# Soccer-Robot_V1_2.net
KiCad netlist of a schematic drawn in EAGLE
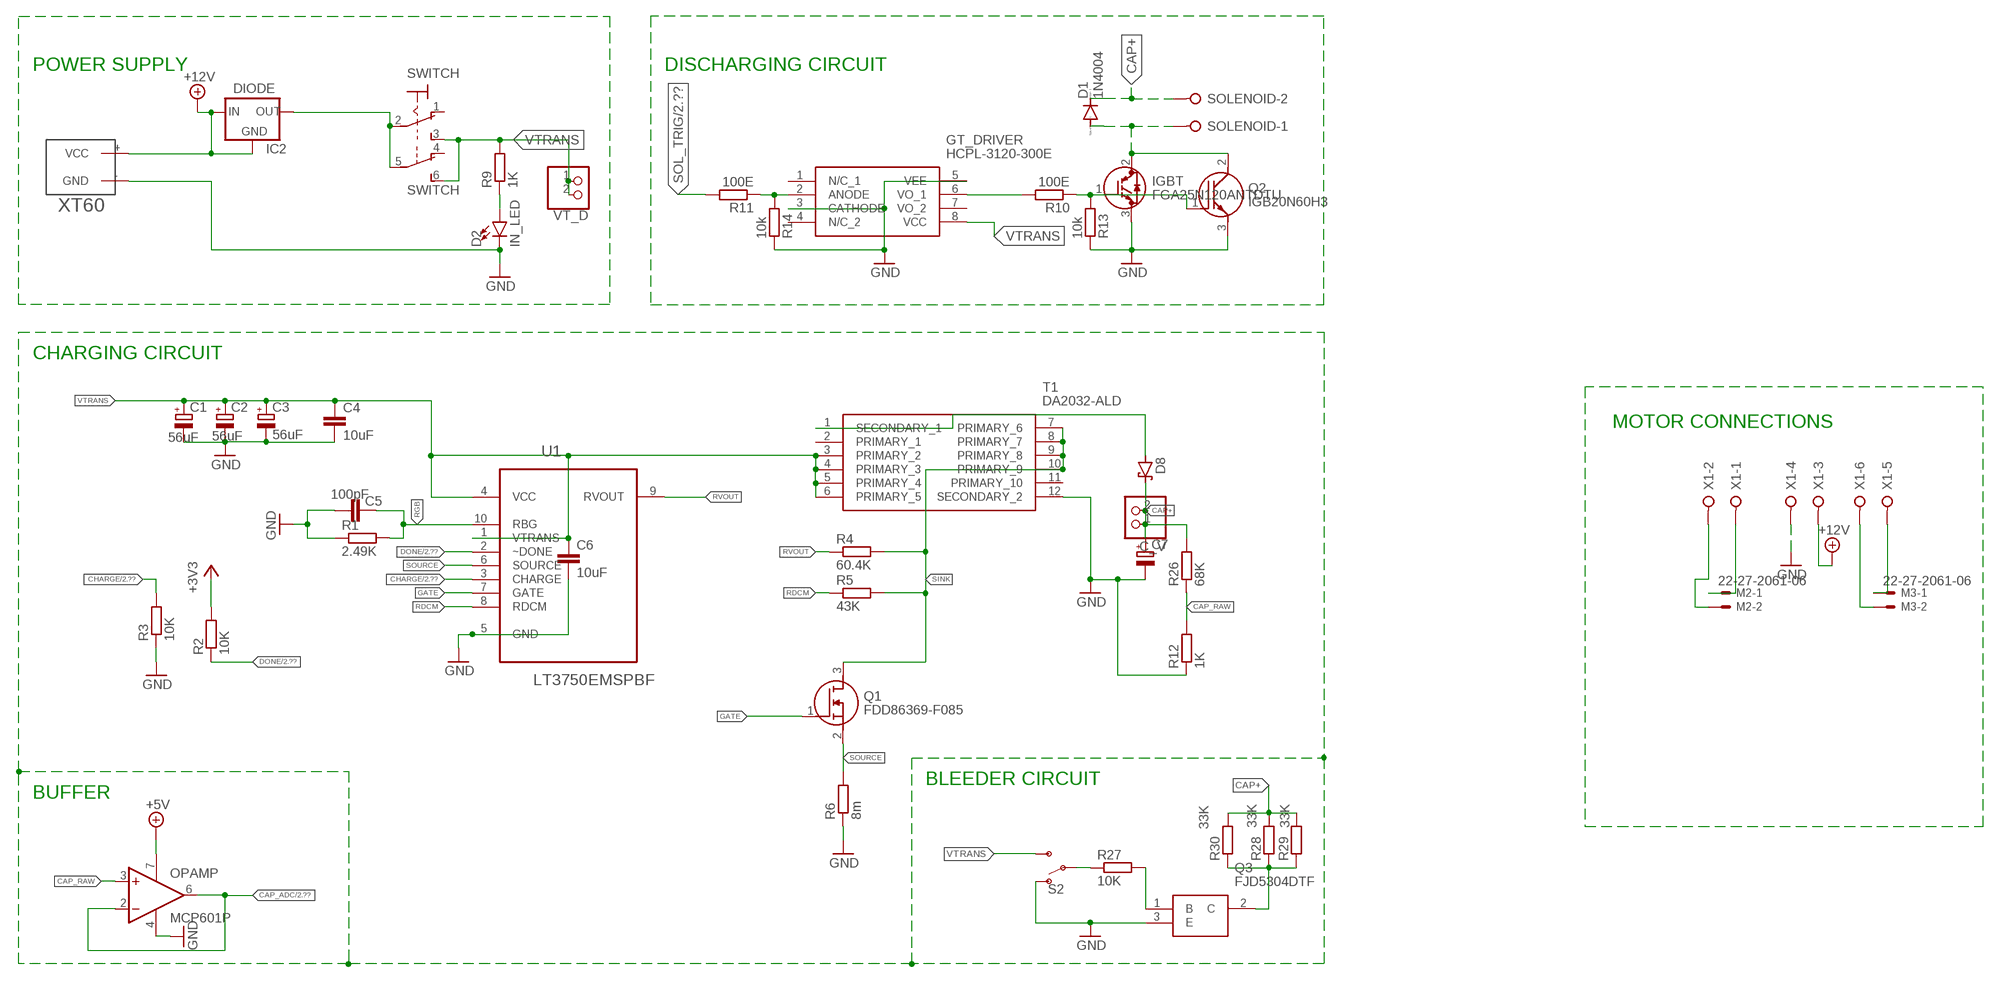
[diagram p0: schematic, sheet 1]
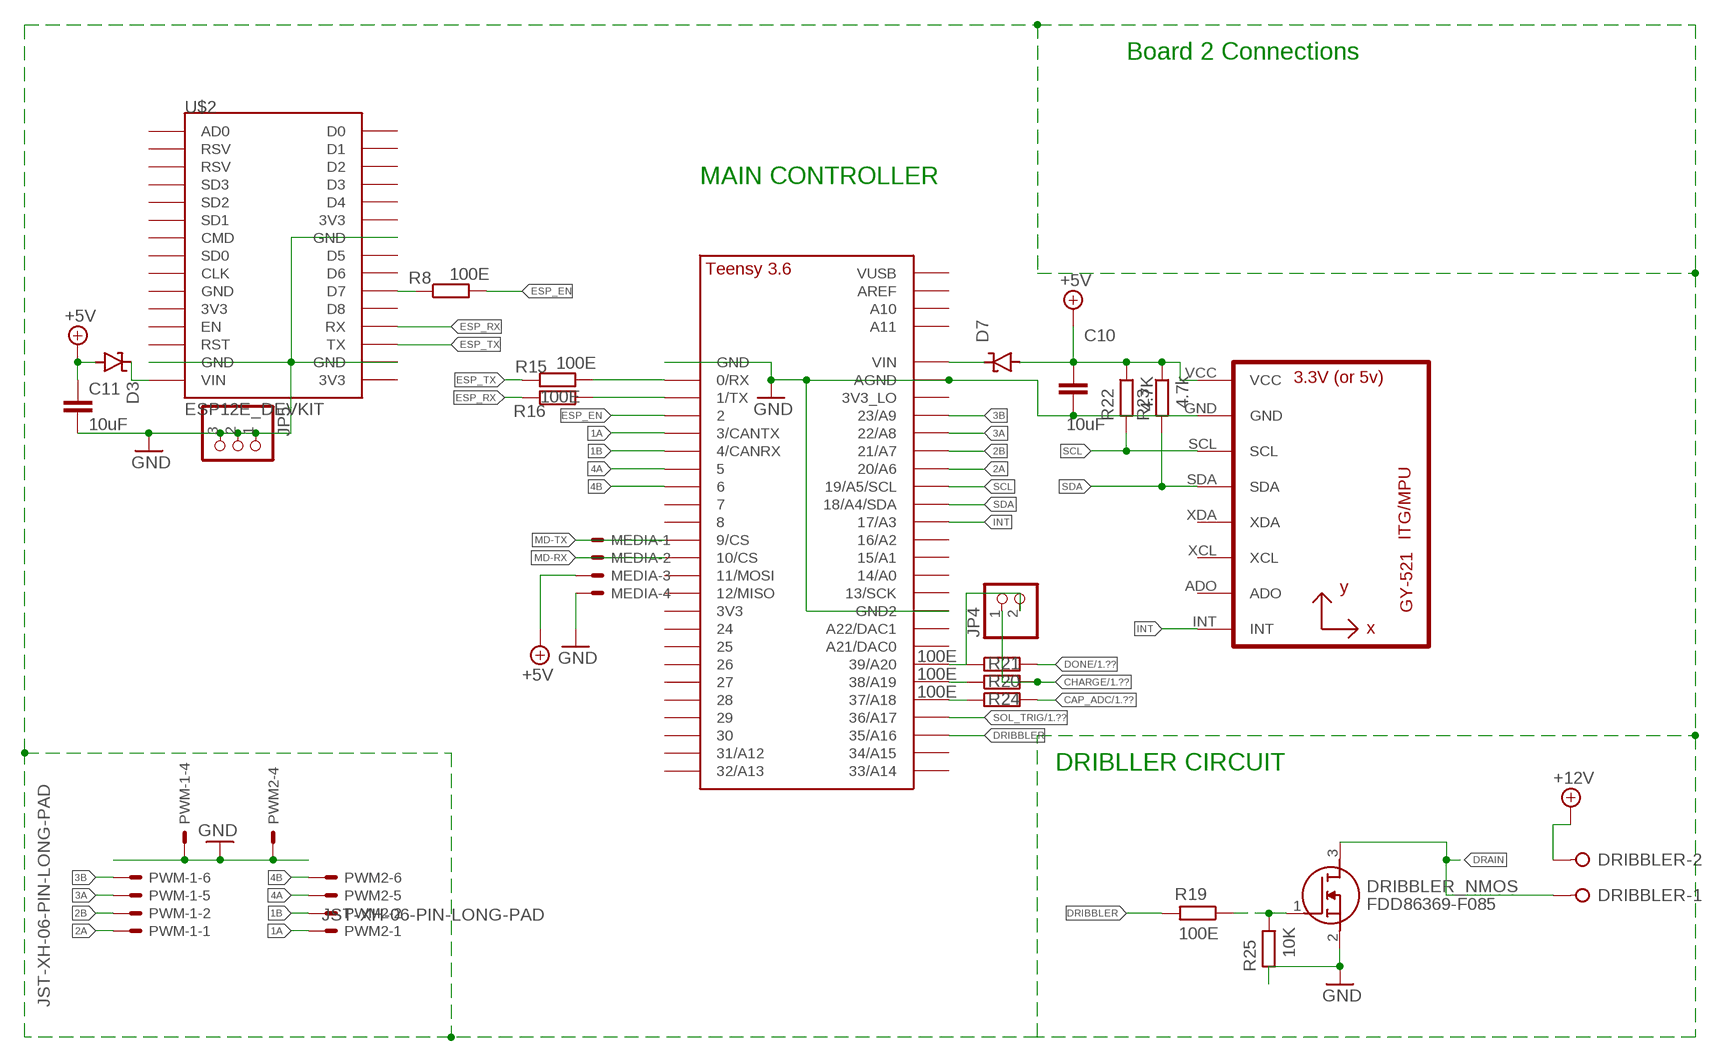
[diagram p1: schematic, sheet 2, part 1 of 2]
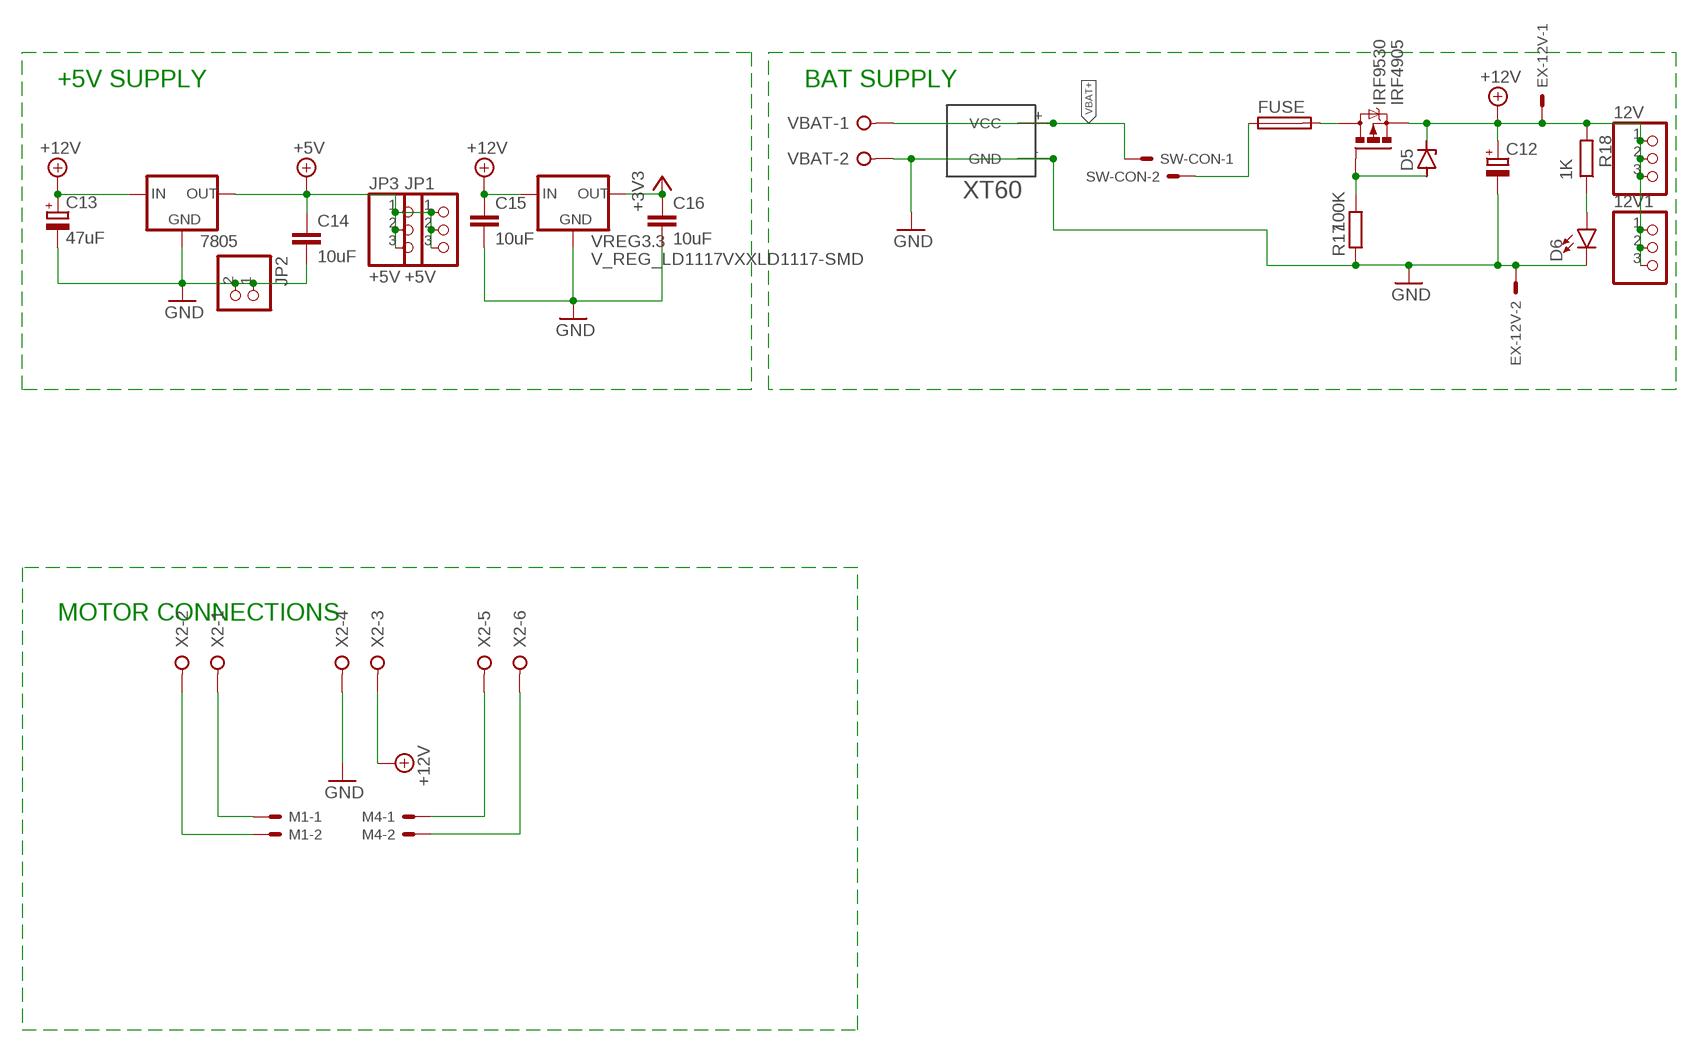
[diagram p2: schematic, sheet 2, part 2 of 2]

(export (version "E")
  (design (tool "Eeschema 10.0.6"))
  (components
    (comp (ref "12V")
      (value "PINHD-1X3")
      (footprint "eagle-import:1X03")
      (libsource (lib "eagle-import") (part "PINHD-1X3"))
    )
    (comp (ref "12V1")
      (value "PINHD-1X3")
      (footprint "eagle-import:1X03")
      (libsource (lib "eagle-import") (part "PINHD-1X3"))
    )
    (comp (ref "7805")
      (value "78XXS")
      (footprint "eagle-import:78XXS")
      (libsource (lib "eagle-import") (part "78XXS"))
    )
    (comp (ref "C10")
      (value "10uF")
      (footprint "eagle-import:C1206")
      (libsource (lib "eagle-import") (part "C-EUC1206"))
    )
    (comp (ref "C11")
      (value "10uF")
      (footprint "eagle-import:C1206")
      (libsource (lib "eagle-import") (part "C-EUC1206"))
    )
    (comp (ref "C12")
      (value "CPOL-EUE2.5-7")
      (footprint "eagle-import:E2,5-7")
      (libsource (lib "eagle-import") (part "CPOL-EUE2.5-7"))
    )
    (comp (ref "C13")
      (value "47uF")
      (footprint "eagle-import:E2,5-7")
      (libsource (lib "eagle-import") (part "CPOL-EUE2.5-7"))
    )
    (comp (ref "C14")
      (value "10uF")
      (footprint "eagle-import:C1206")
      (libsource (lib "eagle-import") (part "C-EUC1206"))
    )
    (comp (ref "C15")
      (value "10uF")
      (footprint "eagle-import:C1206")
      (libsource (lib "eagle-import") (part "C-EUC1206"))
    )
    (comp (ref "C16")
      (value "10uF")
      (footprint "eagle-import:C1206")
      (libsource (lib "eagle-import") (part "C-EUC1206"))
    )
    (comp (ref "D3")
      (value "SUPPRESSOR-SMBG")
      (footprint "eagle-import:SMBG")
      (libsource (lib "eagle-import") (part "SUPPRESSOR-SMBG"))
    )
    (comp (ref "D5")
      (value "ZENER-DIODEDO41Z10")
      (footprint "eagle-import:DO41Z10")
      (libsource (lib "eagle-import") (part "ZENER-DIODEDO41Z10"))
    )
    (comp (ref "D6")
      (value "LED5MM")
      (footprint "eagle-import:LED_5MM")
      (libsource (lib "eagle-import") (part "LED5MM"))
    )
    (comp (ref "D7")
      (value "SUPPRESSOR-SMBG")
      (footprint "eagle-import:SMBG")
      (libsource (lib "eagle-import") (part "SUPPRESSOR-SMBG"))
    )
    (comp (ref "DRIBBLER")
      (value "W237-02P")
      (footprint "eagle-import:W237-132")
      (libsource (lib "eagle-import") (part "W237-02P"))
    )
    (comp (ref "DRIBBLER_NMOS")
      (value "FDD86369-F085")
      (footprint "eagle-import:DPAK3-CASE-369AS")
      (fields (field (name "MOUSER_PART_NUMBER") "512-FDD86369_F085"))
      (libsource (lib "eagle-import") (part "FDD86369-F085"))
    )
    (comp (ref "EX-12V")
      (value "KK-156-2")
      (footprint "eagle-import:KK-156-2")
      (fields (field (name "MF") "MOLEX"))
      (libsource (lib "eagle-import") (part "KK-156-2"))
    )
    (comp (ref "FUSE")
      (value "SH22,5A")
      (footprint "eagle-import:SH22,5A")
      (fields (field (name "MPN") "0031.7701.11"))
      (libsource (lib "eagle-import") (part "SH22,5A"))
    )
    (comp (ref "IRF4905")
      (value "IRF9530")
      (footprint "eagle-import:TO220BV")
      (libsource (lib "eagle-import") (part "IRF9530"))
    )
    (comp (ref "JP1")
      (value "+5V")
      (footprint "eagle-import:1X03")
      (libsource (lib "eagle-import") (part "PINHD-1X3"))
    )
    (comp (ref "JP2")
      (value "PINHD-1X2")
      (footprint "eagle-import:1X02")
      (libsource (lib "eagle-import") (part "PINHD-1X2"))
    )
    (comp (ref "JP3")
      (value "+5V")
      (footprint "eagle-import:1X03")
      (libsource (lib "eagle-import") (part "PINHD-1X3"))
    )
    (comp (ref "JP4")
      (value "PINHD-1X2")
      (footprint "eagle-import:1X02")
      (libsource (lib "eagle-import") (part "PINHD-1X2"))
    )
    (comp (ref "JP5")
      (value "PINHD-1X3")
      (footprint "eagle-import:1X03")
      (libsource (lib "eagle-import") (part "PINHD-1X3"))
    )
    (comp (ref "M1")
      (value "22-27-2061-06")
      (footprint "eagle-import:6410-06")
      (fields (field (name "MF") "MOLEX"))
      (libsource (lib "eagle-import") (part "22-?-0627-2061"))
    )
    (comp (ref "M4")
      (value "22-27-2061-06")
      (footprint "eagle-import:6410-06")
      (fields (field (name "MF") "MOLEX"))
      (libsource (lib "eagle-import") (part "22-?-0627-2061"))
    )
    (comp (ref "MEDIA")
      (value "JST-XH-04-PIN-LONG-PAD")
      (footprint "eagle-import:JST-XH-04-PACKAGE-LONG-PAD")
      (libsource (lib "eagle-import") (part "JST-XH-04-PIN-LONG-PAD"))
    )
    (comp (ref "PWM-1")
      (value "JST-XH-06-PIN-LONG-PAD")
      (footprint "eagle-import:JST-XH-06-PACKAGE-LONG-PAD")
      (libsource (lib "eagle-import") (part "JST-XH-06-PIN-LONG-PAD"))
    )
    (comp (ref "PWM2")
      (value "JST-XH-06-PIN-LONG-PAD")
      (footprint "eagle-import:JST-XH-06-PACKAGE-LONG-PAD")
      (libsource (lib "eagle-import") (part "JST-XH-06-PIN-LONG-PAD"))
    )
    (comp (ref "R8")
      (value "100E")
      (footprint "eagle-import:M1206")
      (libsource (lib "eagle-import") (part "R-EU_M1206"))
    )
    (comp (ref "R15")
      (value "100E")
      (footprint "eagle-import:M1206")
      (libsource (lib "eagle-import") (part "R-EU_M1206"))
    )
    (comp (ref "R16")
      (value "100E")
      (footprint "eagle-import:M1206")
      (libsource (lib "eagle-import") (part "R-EU_M1206"))
    )
    (comp (ref "R17")
      (value "100K")
      (footprint "eagle-import:M1206")
      (libsource (lib "eagle-import") (part "R-EU_M1206"))
    )
    (comp (ref "R18")
      (value "1K")
      (footprint "eagle-import:M1206")
      (libsource (lib "eagle-import") (part "R-EU_M1206"))
    )
    (comp (ref "R19")
      (value "100E")
      (footprint "eagle-import:M1206")
      (libsource (lib "eagle-import") (part "R-EU_M1206"))
    )
    (comp (ref "R20")
      (value "100E")
      (footprint "eagle-import:M1206")
      (libsource (lib "eagle-import") (part "R-EU_M1206"))
    )
    (comp (ref "R21")
      (value "100E")
      (footprint "eagle-import:M1206")
      (libsource (lib "eagle-import") (part "R-EU_M1206"))
    )
    (comp (ref "R22")
      (value "4.7K")
      (footprint "eagle-import:M1206")
      (libsource (lib "eagle-import") (part "R-EU_M1206"))
    )
    (comp (ref "R23")
      (value "4.7k")
      (footprint "eagle-import:M1206")
      (libsource (lib "eagle-import") (part "R-EU_M1206"))
    )
    (comp (ref "R24")
      (value "100E")
      (footprint "eagle-import:M1206")
      (libsource (lib "eagle-import") (part "R-EU_M1206"))
    )
    (comp (ref "R25")
      (value "10K")
      (footprint "eagle-import:M1206")
      (libsource (lib "eagle-import") (part "R-EU_M1206"))
    )
    (comp (ref "SW-CON")
      (value "KK-156-2")
      (footprint "eagle-import:KK-156-2")
      (fields (field (name "MF") "MOLEX"))
      (libsource (lib "eagle-import") (part "KK-156-2"))
    )
    (comp (ref "U$2")
      (value "ESP12E_DEVKIT")
      (footprint "eagle-import:ESP12E_DEVKIT")
      (libsource (lib "eagle-import") (part "ESP12E_DEVKIT"))
    )
    (comp (ref "U$3")
      (value "TEENSY_3.5/3.6_BASIC")
      (footprint "eagle-import:TEENSY_3.5_3.6_BASIC")
      (libsource (lib "eagle-import") (part "TEENSY_3.5/3.6_BASIC"))
    )
    (comp (ref "U2")
      (value "GY-521MPU6050")
      (footprint "eagle-import:GY-521")
      (libsource (lib "eagle-import") (part "GY-521MPU6050"))
    )
    (comp (ref "VBAT")
      (value "W237-02P")
      (footprint "eagle-import:W237-132")
      (libsource (lib "eagle-import") (part "W237-02P"))
    )
    (comp (ref "VBAT2")
      (value "XT60")
      (footprint "eagle-import:XT60")
      (libsource (lib "eagle-import") (part "XT60"))
    )
    (comp (ref "VREG3.3")
      (value "V_REG_LD1117VXXLD1117-SMD")
      (footprint "eagle-import:SOT223")
      (libsource (lib "eagle-import") (part "V_REG_LD1117VXXLD1117-SMD"))
    )
    (comp (ref "X2")
      (value "W237-06P")
      (footprint "eagle-import:W237-6P")
      (libsource (lib "eagle-import") (part "W237-06P"))
    )
    (comp (ref "C1")
      (value "56uF")
      (footprint "eagle-import:E2,5-5")
      (libsource (lib "eagle-import") (part "CPOL-EUE2.5-5"))
    )
    (comp (ref "C2")
      (value "56uF")
      (footprint "eagle-import:E2,5-5")
      (libsource (lib "eagle-import") (part "CPOL-EUE2.5-5"))
    )
    (comp (ref "C3")
      (value "56uF")
      (footprint "eagle-import:E2,5-5")
      (libsource (lib "eagle-import") (part "CPOL-EUE2.5-5"))
    )
    (comp (ref "C4")
      (value "10uF")
      (footprint "eagle-import:C1206")
      (libsource (lib "eagle-import") (part "C-EUC1206"))
    )
    (comp (ref "C5")
      (value "100pF")
      (footprint "eagle-import:C1206")
      (libsource (lib "eagle-import") (part "C-EUC1206"))
    )
    (comp (ref "C6")
      (value "10uF")
      (footprint "eagle-import:C1206")
      (libsource (lib "eagle-import") (part "C-EUC1206"))
    )
    (comp (ref "C7")
      (value "CPOL-EUE10-30")
      (footprint "eagle-import:EB30D")
      (libsource (lib "eagle-import") (part "CPOL-EUE10-30"))
    )
    (comp (ref "C_V")
      (value "PINHD-1X2")
      (footprint "eagle-import:1X02")
      (libsource (lib "eagle-import") (part "PINHD-1X2"))
    )
    (comp (ref "D1")
      (value "1N4004")
      (footprint "eagle-import:DO41-10")
      (libsource (lib "eagle-import") (part "1N4004"))
    )
    (comp (ref "D2")
      (value "IN_LED")
      (footprint "eagle-import:LED_5MM")
      (libsource (lib "eagle-import") (part "LED5MM"))
    )
    (comp (ref "D8")
      (value "SCHOTTKY-DIODESMC")
      (footprint "eagle-import:SMC")
      (libsource (lib "eagle-import") (part "SCHOTTKY-DIODESMC"))
    )
    (comp (ref "GT_DRIVER")
      (value "HCPL-3120-300E")
      (footprint "eagle-import:HCPL-3120-GULL-WING")
      (fields (field (name "MOUSER_PART_NUMBER") "630-HCPL-3120-300E"))
      (libsource (lib "eagle-import") (part "HCPL-3120-300E"))
    )
    (comp (ref "IC2")
      (value "DIODE")
      (footprint "eagle-import:TO252")
      (libsource (lib "eagle-import") (part "LM1117TO252"))
    )
    (comp (ref "IGBT")
      (value "FGA25N120ANTDTU")
      (footprint "eagle-import:TO545P500X1560X2420-3P")
      (fields (field (name "MOUSER_PART_NUMBER") "512-FGA25N120ANTDTU"))
      (libsource (lib "eagle-import") (part "FGA25N120ANTDTU"))
    )
    (comp (ref "M2")
      (value "22-27-2061-06")
      (footprint "eagle-import:6410-06")
      (fields (field (name "MF") "MOLEX"))
      (libsource (lib "eagle-import") (part "22-?-0627-2061"))
    )
    (comp (ref "M3")
      (value "22-27-2061-06")
      (footprint "eagle-import:6410-06")
      (fields (field (name "MF") "MOLEX"))
      (libsource (lib "eagle-import") (part "22-?-0627-2061"))
    )
    (comp (ref "OPAMP")
      (value "MCP601P")
      (footprint "eagle-import:DIL08")
      (libsource (lib "eagle-import") (part "MCP601P"))
    )
    (comp (ref "Q1")
      (value "FDD86369-F085")
      (footprint "eagle-import:DPAK3-CASE-369AS")
      (fields (field (name "MOUSER_PART_NUMBER") "512-FDD86369_F085"))
      (libsource (lib "eagle-import") (part "FDD86369-F085"))
    )
    (comp (ref "Q2")
      (value "IGB20N60H3")
      (footprint "eagle-import:IDB30E60")
      (fields (field (name "MOUSER_PART_NUMBER") "726-IGB20N60H3"))
      (libsource (lib "eagle-import") (part "IGB20N60H3"))
    )
    (comp (ref "Q3")
      (value "FJD5304DTF")
      (footprint "eagle-import:FJD5304DTF")
      (fields (field (name "MOUSER_PART_NUMBER") "512-FJD5304DTF"))
      (libsource (lib "eagle-import") (part "FJD5304DTF"))
    )
    (comp (ref "R1")
      (value "2.49K")
      (footprint "eagle-import:M1206")
      (libsource (lib "eagle-import") (part "R-EU_M1206"))
    )
    (comp (ref "R2")
      (value "10K")
      (footprint "eagle-import:M1206")
      (libsource (lib "eagle-import") (part "R-EU_M1206"))
    )
    (comp (ref "R3")
      (value "10K")
      (footprint "eagle-import:M1206")
      (libsource (lib "eagle-import") (part "R-EU_M1206"))
    )
    (comp (ref "R4")
      (value "60.4K")
      (footprint "eagle-import:M1206")
      (libsource (lib "eagle-import") (part "R-EU_M1206"))
    )
    (comp (ref "R5")
      (value "43K")
      (footprint "eagle-import:M1206")
      (libsource (lib "eagle-import") (part "R-EU_M1206"))
    )
    (comp (ref "R6")
      (value "8m")
      (footprint "eagle-import:M1206")
      (libsource (lib "eagle-import") (part "R-EU_M1206"))
    )
    (comp (ref "R9")
      (value "1K")
      (footprint "eagle-import:M1206")
      (libsource (lib "eagle-import") (part "R-EU_M1206"))
    )
    (comp (ref "R10")
      (value "100E")
      (footprint "eagle-import:M1206")
      (libsource (lib "eagle-import") (part "R-EU_M1206"))
    )
    (comp (ref "R11")
      (value "100E")
      (footprint "eagle-import:M1206")
      (libsource (lib "eagle-import") (part "R-EU_M1206"))
    )
    (comp (ref "R12")
      (value "1K")
      (footprint "eagle-import:M1206")
      (libsource (lib "eagle-import") (part "R-EU_M1206"))
    )
    (comp (ref "R13")
      (value "10k")
      (footprint "eagle-import:M1206")
      (libsource (lib "eagle-import") (part "R-EU_M1206"))
    )
    (comp (ref "R14")
      (value "10k")
      (footprint "eagle-import:M1206")
      (libsource (lib "eagle-import") (part "R-EU_M1206"))
    )
    (comp (ref "R26")
      (value "68K")
      (footprint "eagle-import:M1206")
      (libsource (lib "eagle-import") (part "R-EU_M1206"))
    )
    (comp (ref "R27")
      (value "10K")
      (footprint "eagle-import:M1206")
      (libsource (lib "eagle-import") (part "R-EU_M1206"))
    )
    (comp (ref "R28")
      (value "33K")
      (footprint "eagle-import:M1206")
      (libsource (lib "eagle-import") (part "R-EU_M1206"))
    )
    (comp (ref "R29")
      (value "33K")
      (footprint "eagle-import:M1206")
      (libsource (lib "eagle-import") (part "R-EU_M1206"))
    )
    (comp (ref "R30")
      (value "33K")
      (footprint "eagle-import:M1206")
      (libsource (lib "eagle-import") (part "R-EU_M1206"))
    )
    (comp (ref "S2")
      (value "SWITCH-SPDT-PTH-11.6X4.0MM")
      (footprint "eagle-import:SWITCH_SPDT_PTH_11.6X4.0MM")
      (libsource (lib "eagle-import") (part "SWITCH-SPDT-PTH-11.6X4.0MM"))
    )
    (comp (ref "SOLENOID")
      (value "W237-02P")
      (footprint "eagle-import:W237-132")
      (libsource (lib "eagle-import") (part "W237-02P"))
    )
    (comp (ref "SWITCH")
      (value "320-938")
      (footprint "eagle-import:320-938")
      (libsource (lib "eagle-import") (part "320-938"))
    )
    (comp (ref "T1")
      (value "DA2032-ALD")
      (footprint "eagle-import:SOP250P2197X889-12N")
      (fields (field (name "MOUSER_PART_NUMBER") "994-DA2032-ALD"))
      (libsource (lib "eagle-import") (part "DA2032-ALD"))
    )
    (comp (ref "U$1")
      (value "XT60")
      (footprint "eagle-import:XT60")
      (libsource (lib "eagle-import") (part "XT60"))
    )
    (comp (ref "U1")
      (value "LT3750EMSPBF")
      (footprint "eagle-import:SOP50P490X110-10N")
      (fields (field (name "MPN") "LT3750EMS#PBF"))
      (libsource (lib "eagle-import") (part "LT3750EMSPBF"))
    )
    (comp (ref "VT_D")
      (value "PINHD-1X2")
      (footprint "eagle-import:1X02")
      (libsource (lib "eagle-import") (part "PINHD-1X2"))
    )
    (comp (ref "X1")
      (value "W237-06P")
      (footprint "eagle-import:W237-6P")
      (libsource (lib "eagle-import") (part "W237-06P"))
    )
  )
  (nets
    (net (code "1") (name "+3V3") (class "Default")
      (node (ref "C16") (pin "1") (pinfunction "1_1") (pintype "passive"))
      (node (ref "R2") (pin "2") (pinfunction "2_2") (pintype "passive"))
      (node (ref "VREG3.3") (pin "2") (pinfunction "OUT_2") (pintype "passive"))
      (node (ref "VREG3.3") (pin "4") (pinfunction "OUT_4") (pintype "passive"))
    )
    (net (code "2") (name "+5V") (class "Default")
      (node (ref "7805") (pin "OUT") (pinfunction "OUT_OUT") (pintype "passive"))
      (node (ref "C10") (pin "1") (pinfunction "1_1") (pintype "passive"))
      (node (ref "C11") (pin "1") (pinfunction "1_1") (pintype "passive"))
      (node (ref "C14") (pin "1") (pinfunction "1_1") (pintype "passive"))
      (node (ref "D3") (pin "A") (pinfunction "A_A") (pintype "passive"))
      (node (ref "D7") (pin "A") (pinfunction "A_A") (pintype "passive"))
      (node (ref "JP1") (pin "1") (pinfunction "1_1") (pintype "passive"))
      (node (ref "JP1") (pin "2") (pinfunction "2_2") (pintype "passive"))
      (node (ref "JP1") (pin "3") (pinfunction "3_3") (pintype "passive"))
      (node (ref "JP3") (pin "1") (pinfunction "1_1") (pintype "passive"))
      (node (ref "JP3") (pin "2") (pinfunction "2_2") (pintype "passive"))
      (node (ref "JP3") (pin "3") (pinfunction "3_3") (pintype "passive"))
      (node (ref "MEDIA") (pin "3") (pinfunction "S_3") (pintype "passive"))
      (node (ref "OPAMP") (pin "7") (pinfunction "V+_7") (pintype "power_in"))
      (node (ref "R22") (pin "1") (pinfunction "1_1") (pintype "passive"))
      (node (ref "R23") (pin "1") (pinfunction "1_1") (pintype "passive"))
      (node (ref "U2") (pin "VCC") (pinfunction "VCC_VCC") (pintype "bidirectional"))
    )
    (net (code "3") (name "+12V") (class "Default")
      (node (ref "12V") (pin "1") (pinfunction "1_1") (pintype "passive"))
      (node (ref "12V") (pin "2") (pinfunction "2_2") (pintype "passive"))
      (node (ref "12V") (pin "3") (pinfunction "3_3") (pintype "passive"))
      (node (ref "12V1") (pin "1") (pinfunction "1_1") (pintype "passive"))
      (node (ref "12V1") (pin "2") (pinfunction "2_2") (pintype "passive"))
      (node (ref "12V1") (pin "3") (pinfunction "3_3") (pintype "passive"))
      (node (ref "7805") (pin "IN") (pinfunction "IN_IN") (pintype "input"))
      (node (ref "C12") (pin "+") (pinfunction "+_+") (pintype "passive"))
      (node (ref "C13") (pin "+") (pinfunction "+_+") (pintype "passive"))
      (node (ref "C15") (pin "1") (pinfunction "1_1") (pintype "passive"))
      (node (ref "D5") (pin "C") (pinfunction "C_C") (pintype "passive"))
      (node (ref "DRIBBLER") (pin "2") (pinfunction "KL_2") (pintype "passive"))
      (node (ref "EX-12V") (pin "1") (pinfunction "S_1") (pintype "passive"))
      (node (ref "IC2") (pin "1") (pinfunction "GND_1") (pintype "input"))
      (node (ref "IC2") (pin "2") (pinfunction "IN_2") (pintype "input"))
      (node (ref "IRF4905") (pin "S") (pinfunction "S_S") (pintype "passive"))
      (node (ref "R18") (pin "2") (pinfunction "2_2") (pintype "passive"))
      (node (ref "U$1") (pin "+") (pinfunction "VCC_+") (pintype "bidirectional"))
      (node (ref "VREG3.3") (pin "3") (pinfunction "IN_3") (pintype "input"))
      (node (ref "X1") (pin "3") (pinfunction "KL_3") (pintype "passive"))
      (node (ref "X2") (pin "3") (pinfunction "KL_3") (pintype "passive"))
    )
    (net (code "4") (name "1A") (class "Default")
      (node (ref "PWM2") (pin "1") (pinfunction "S_1") (pintype "passive"))
      (node (ref "U$3") (pin "3/CANTX") (pinfunction "3/CANTX_3/CANTX") (pintype "bidirectional"))
    )
    (net (code "5") (name "1B") (class "Default")
      (node (ref "PWM2") (pin "2") (pinfunction "S_2") (pintype "passive"))
      (node (ref "U$3") (pin "4/CANRX") (pinfunction "4/CANRX_4/CANRX") (pintype "bidirectional"))
    )
    (net (code "6") (name "2A") (class "Default")
      (node (ref "PWM-1") (pin "1") (pinfunction "S_1") (pintype "passive"))
      (node (ref "U$3") (pin "20/A6") (pinfunction "20/A6_20/A6") (pintype "bidirectional"))
    )
    (net (code "7") (name "2B") (class "Default")
      (node (ref "PWM-1") (pin "2") (pinfunction "S_2") (pintype "passive"))
      (node (ref "U$3") (pin "21/A7") (pinfunction "21/A7_21/A7") (pintype "bidirectional"))
    )
    (net (code "8") (name "3A") (class "Default")
      (node (ref "PWM-1") (pin "5") (pinfunction "S_5") (pintype "passive"))
      (node (ref "U$3") (pin "22/A8") (pinfunction "22/A8_22/A8") (pintype "bidirectional"))
    )
    (net (code "9") (name "3B") (class "Default")
      (node (ref "PWM-1") (pin "6") (pinfunction "S_6") (pintype "passive"))
      (node (ref "U$3") (pin "23/A9") (pinfunction "23/A9_23/A9") (pintype "bidirectional"))
    )
    (net (code "10") (name "4A") (class "Default")
      (node (ref "PWM2") (pin "5") (pinfunction "S_5") (pintype "passive"))
      (node (ref "U$3") (pin "5") (pinfunction "5_5") (pintype "bidirectional"))
    )
    (net (code "11") (name "4B") (class "Default")
      (node (ref "PWM2") (pin "6") (pinfunction "S_6") (pintype "passive"))
      (node (ref "U$3") (pin "6") (pinfunction "6_6") (pintype "bidirectional"))
    )
    (net (code "12") (name "CAP+") (class "Default")
      (node (ref "C7") (pin "+") (pinfunction "+_+") (pintype "passive"))
      (node (ref "C_V") (pin "1") (pinfunction "1_1") (pintype "passive"))
      (node (ref "C_V") (pin "2") (pinfunction "2_2") (pintype "passive"))
      (node (ref "D1") (pin "C") (pinfunction "C_C") (pintype "passive"))
      (node (ref "D8") (pin "C") (pinfunction "C_C") (pintype "passive"))
      (node (ref "R26") (pin "2") (pinfunction "2_2") (pintype "passive"))
      (node (ref "R28") (pin "2") (pinfunction "2_2") (pintype "passive"))
      (node (ref "R29") (pin "2") (pinfunction "2_2") (pintype "passive"))
      (node (ref "R30") (pin "2") (pinfunction "2_2") (pintype "passive"))
      (node (ref "SOLENOID") (pin "2") (pinfunction "KL_2") (pintype "passive"))
    )
    (net (code "13") (name "CAP_ADC") (class "Default")
      (node (ref "OPAMP") (pin "2") (pinfunction "-IN_2") (pintype "input"))
      (node (ref "OPAMP") (pin "6") (pinfunction "OUT_6") (pintype "output"))
      (node (ref "R24") (pin "2") (pinfunction "2_2") (pintype "passive"))
    )
    (net (code "14") (name "CAP_RAW") (class "Default")
      (node (ref "OPAMP") (pin "3") (pinfunction "+IN_3") (pintype "input"))
      (node (ref "R12") (pin "2") (pinfunction "2_2") (pintype "passive"))
      (node (ref "R26") (pin "1") (pinfunction "1_1") (pintype "passive"))
    )
    (net (code "15") (name "CHARGE") (class "Default")
      (node (ref "JP4") (pin "1") (pinfunction "1_1") (pintype "passive"))
      (node (ref "R20") (pin "2") (pinfunction "2_2") (pintype "passive"))
      (node (ref "R3") (pin "2") (pinfunction "2_2") (pintype "passive"))
      (node (ref "U1") (pin "3") (pinfunction "CHARGE_3") (pintype "input"))
    )
    (net (code "16") (name "DONE") (class "Default")
      (node (ref "R2") (pin "1") (pinfunction "1_1") (pintype "passive"))
      (node (ref "R21") (pin "2") (pinfunction "2_2") (pintype "passive"))
      (node (ref "U1") (pin "2") (pinfunction "~{DONE}_2") (pintype "input"))
    )
    (net (code "17") (name "DRAIN") (class "Default")
      (node (ref "DRIBBLER") (pin "1") (pinfunction "KL_1") (pintype "passive"))
      (node (ref "DRIBBLER_NMOS") (pin "3") (pinfunction "D_3") (pintype "bidirectional"))
    )
    (net (code "18") (name "DRIBBLER") (class "Default")
      (node (ref "R19") (pin "2") (pinfunction "2_2") (pintype "passive"))
      (node (ref "U$3") (pin "35/A16") (pinfunction "35/A16_35/A16") (pintype "bidirectional"))
    )
    (net (code "19") (name "ESP_EN") (class "Default")
      (node (ref "R8") (pin "2") (pinfunction "2_2") (pintype "passive"))
      (node (ref "U$3") (pin "2") (pinfunction "2_2") (pintype "bidirectional"))
    )
    (net (code "20") (name "ESP_RX") (class "Default")
      (node (ref "R16") (pin "1") (pinfunction "1_1") (pintype "passive"))
      (node (ref "U$2") (pin "RX") (pinfunction "RX_RX") (pintype "bidirectional"))
    )
    (net (code "21") (name "ESP_TX") (class "Default")
      (node (ref "R15") (pin "1") (pinfunction "1_1") (pintype "passive"))
      (node (ref "U$2") (pin "TX") (pinfunction "TX_TX") (pintype "bidirectional"))
    )
    (net (code "22") (name "GATE") (class "Default")
      (node (ref "Q1") (pin "1") (pinfunction "G_1") (pintype "bidirectional"))
      (node (ref "U1") (pin "7") (pinfunction "GATE_7") (pintype "input"))
    )
    (net (code "23") (name "GND") (class "Default")
      (node (ref "7805") (pin "GND") (pinfunction "GND_GND") (pintype "input"))
      (node (ref "C1") (pin "-") (pinfunction "-_-") (pintype "passive"))
      (node (ref "C10") (pin "2") (pinfunction "2_2") (pintype "passive"))
      (node (ref "C11") (pin "2") (pinfunction "2_2") (pintype "passive"))
      (node (ref "C12") (pin "-") (pinfunction "-_-") (pintype "passive"))
      (node (ref "C13") (pin "-") (pinfunction "-_-") (pintype "passive"))
      (node (ref "C14") (pin "2") (pinfunction "2_2") (pintype "passive"))
      (node (ref "C15") (pin "2") (pinfunction "2_2") (pintype "passive"))
      (node (ref "C16") (pin "2") (pinfunction "2_2") (pintype "passive"))
      (node (ref "C2") (pin "-") (pinfunction "-_-") (pintype "passive"))
      (node (ref "C3") (pin "-") (pinfunction "-_-") (pintype "passive"))
      (node (ref "C4") (pin "2") (pinfunction "2_2") (pintype "passive"))
      (node (ref "C5") (pin "2") (pinfunction "2_2") (pintype "passive"))
      (node (ref "C6") (pin "2") (pinfunction "2_2") (pintype "passive"))
      (node (ref "C7") (pin "-") (pinfunction "-_-") (pintype "passive"))
      (node (ref "D2") (pin "K") (pinfunction "C_K") (pintype "passive"))
      (node (ref "D6") (pin "K") (pinfunction "C_K") (pintype "passive"))
      (node (ref "DRIBBLER_NMOS") (pin "2") (pinfunction "S_2") (pintype "bidirectional"))
      (node (ref "EX-12V") (pin "2") (pinfunction "S_2") (pintype "passive"))
      (node (ref "GT_DRIVER") (pin "3") (pinfunction "CATHODE_3") (pintype "bidirectional"))
      (node (ref "GT_DRIVER") (pin "5") (pinfunction "VEE_5") (pintype "bidirectional"))
      (node (ref "IGBT") (pin "3") (pinfunction "E_3") (pintype "bidirectional"))
      (node (ref "JP2") (pin "1") (pinfunction "1_1") (pintype "passive"))
      (node (ref "JP2") (pin "2") (pinfunction "2_2") (pintype "passive"))
      (node (ref "JP5") (pin "1") (pinfunction "1_1") (pintype "passive"))
      (node (ref "JP5") (pin "2") (pinfunction "2_2") (pintype "passive"))
      (node (ref "JP5") (pin "3") (pinfunction "3_3") (pintype "passive"))
      (node (ref "MEDIA") (pin "4") (pinfunction "S_4") (pintype "passive"))
      (node (ref "OPAMP") (pin "4") (pinfunction "V-_4") (pintype "power_in"))
      (node (ref "PWM-1") (pin "4") (pinfunction "S_4") (pintype "passive"))
      (node (ref "PWM2") (pin "4") (pinfunction "S_4") (pintype "passive"))
      (node (ref "Q2") (pin "3") (pinfunction "E_3") (pintype "bidirectional"))
      (node (ref "Q3") (pin "3") (pinfunction "E_3") (pintype "bidirectional"))
      (node (ref "R1") (pin "1") (pinfunction "1_1") (pintype "passive"))
      (node (ref "R12") (pin "1") (pinfunction "1_1") (pintype "passive"))
      (node (ref "R13") (pin "2") (pinfunction "2_2") (pintype "passive"))
      (node (ref "R14") (pin "2") (pinfunction "2_2") (pintype "passive"))
      (node (ref "R17") (pin "1") (pinfunction "1_1") (pintype "passive"))
      (node (ref "R25") (pin "2") (pinfunction "2_2") (pintype "passive"))
      (node (ref "R3") (pin "1") (pinfunction "1_1") (pintype "passive"))
      (node (ref "R6") (pin "1") (pinfunction "1_1") (pintype "passive"))
      (node (ref "S2") (pin "1") (pinfunction "O_1") (pintype "passive"))
      (node (ref "T1") (pin "12") (pinfunction "SECONDARY_2_12") (pintype "bidirectional"))
      (node (ref "U$1") (pin "-") (pinfunction "GND_-") (pintype "bidirectional"))
      (node (ref "U$2") (pin "GND@1") (pinfunction "GND_GND@1") (pintype "bidirectional"))
      (node (ref "U$2") (pin "GND@2") (pinfunction "GND_GND@2") (pintype "bidirectional"))
      (node (ref "U$2") (pin "GND@3") (pinfunction "GND_GND@3") (pintype "bidirectional"))
      (node (ref "U$3") (pin "AGND") (pinfunction "AGND_AGND") (pintype "bidirectional"))
      (node (ref "U$3") (pin "GND") (pinfunction "GND_GND") (pintype "bidirectional"))
      (node (ref "U$3") (pin "GND2") (pinfunction "GND2_GND2") (pintype "bidirectional"))
      (node (ref "U1") (pin "5") (pinfunction "GND_5") (pintype "passive"))
      (node (ref "U2") (pin "GND") (pinfunction "GND_GND") (pintype "bidirectional"))
      (node (ref "VBAT") (pin "2") (pinfunction "KL_2") (pintype "passive"))
      (node (ref "VBAT2") (pin "-") (pinfunction "GND_-") (pintype "bidirectional"))
      (node (ref "VREG3.3") (pin "1") (pinfunction "GND_1") (pintype "input"))
      (node (ref "X1") (pin "4") (pinfunction "KL_4") (pintype "passive"))
      (node (ref "X2") (pin "4") (pinfunction "KL_4") (pintype "passive"))
    )
    (net (code "24") (name "INT") (class "Default")
      (node (ref "U$3") (pin "17/A3") (pinfunction "17/A3_17/A3") (pintype "bidirectional"))
      (node (ref "U2") (pin "INT") (pinfunction "INT_INT") (pintype "bidirectional"))
    )
    (net (code "25") (name "MD-RX") (class "Default")
      (node (ref "MEDIA") (pin "2") (pinfunction "S_2") (pintype "passive"))
      (node (ref "U$3") (pin "10/CS") (pinfunction "10/CS_10/CS") (pintype "bidirectional"))
    )
    (net (code "26") (name "MD-TX") (class "Default")
      (node (ref "MEDIA") (pin "1") (pinfunction "S_1") (pintype "passive"))
      (node (ref "U$3") (pin "9/CS") (pinfunction "9/CS_9/CS") (pintype "bidirectional"))
    )
    (net (code "27") (name "Net-(D2-PadA)") (class "Default")
      (node (ref "D2") (pin "A") (pinfunction "A_A") (pintype "passive"))
      (node (ref "R9") (pin "1") (pinfunction "1_1") (pintype "passive"))
    )
    (net (code "28") (name "Net-(D3-PadC)") (class "Default")
      (node (ref "D3") (pin "C") (pinfunction "C_C") (pintype "passive"))
      (node (ref "U$2") (pin "VIN") (pinfunction "VIN_VIN") (pintype "bidirectional"))
    )
    (net (code "29") (name "Net-(D5-PadA)") (class "Default")
      (node (ref "D5") (pin "A") (pinfunction "A_A") (pintype "passive"))
      (node (ref "IRF4905") (pin "G") (pinfunction "G_G") (pintype "passive"))
      (node (ref "R17") (pin "2") (pinfunction "2_2") (pintype "passive"))
    )
    (net (code "30") (name "Net-(D6-PadA)") (class "Default")
      (node (ref "D6") (pin "A") (pinfunction "A_A") (pintype "passive"))
      (node (ref "R18") (pin "1") (pinfunction "1_1") (pintype "passive"))
    )
    (net (code "31") (name "Net-(D7-PadC)") (class "Default")
      (node (ref "D7") (pin "C") (pinfunction "C_C") (pintype "passive"))
      (node (ref "U$3") (pin "VIN") (pinfunction "VIN_VIN") (pintype "bidirectional"))
    )
    (net (code "32") (name "Net-(DRIBBLER_NMOS-G)") (class "Default")
      (node (ref "DRIBBLER_NMOS") (pin "1") (pinfunction "G_1") (pintype "bidirectional"))
      (node (ref "R19") (pin "1") (pinfunction "1_1") (pintype "passive"))
      (node (ref "R25") (pin "1") (pinfunction "1_1") (pintype "passive"))
    )
    (net (code "33") (name "Net-(FUSE-Pad2)") (class "Default")
      (node (ref "FUSE") (pin "2") (pinfunction "2_2") (pintype "passive"))
      (node (ref "IRF4905") (pin "D") (pinfunction "D_D") (pintype "passive"))
    )
    (net (code "34") (name "Net-(GT_DRIVER-ANODE)") (class "Default")
      (node (ref "GT_DRIVER") (pin "2") (pinfunction "ANODE_2") (pintype "bidirectional"))
      (node (ref "R11") (pin "1") (pinfunction "1_1") (pintype "passive"))
      (node (ref "R14") (pin "1") (pinfunction "1_1") (pintype "passive"))
    )
    (net (code "35") (name "Net-(GT_DRIVER-VO_1)") (class "Default")
      (node (ref "GT_DRIVER") (pin "6") (pinfunction "VO_1_6") (pintype "bidirectional"))
      (node (ref "R10") (pin "2") (pinfunction "2_2") (pintype "passive"))
    )
    (net (code "36") (name "Net-(IC2-OUT)") (class "Default")
      (node (ref "IC2") (pin "3") (pinfunction "OUT_3") (pintype "passive"))
      (node (ref "SWITCH") (pin "2") (pinfunction "P_2") (pintype "passive"))
      (node (ref "SWITCH") (pin "5") (pinfunction "P_5") (pintype "passive"))
    )
    (net (code "37") (name "Net-(IGBT-C)") (class "Default")
      (node (ref "D1") (pin "A") (pinfunction "A_A") (pintype "passive"))
      (node (ref "IGBT") (pin "2") (pinfunction "C_2") (pintype "bidirectional"))
      (node (ref "Q2") (pin "2") (pinfunction "C_2") (pintype "bidirectional"))
      (node (ref "SOLENOID") (pin "1") (pinfunction "KL_1") (pintype "passive"))
    )
    (net (code "38") (name "Net-(IGBT-G)") (class "Default")
      (node (ref "IGBT") (pin "1") (pinfunction "G_1") (pintype "bidirectional"))
      (node (ref "Q2") (pin "1") (pinfunction "G_1") (pintype "bidirectional"))
      (node (ref "R10") (pin "1") (pinfunction "1_1") (pintype "passive"))
      (node (ref "R13") (pin "1") (pinfunction "1_1") (pintype "passive"))
    )
    (net (code "39") (name "Net-(JP4-Pad2)") (class "Default")
      (node (ref "JP4") (pin "2") (pinfunction "2_2") (pintype "passive"))
      (node (ref "R21") (pin "1") (pinfunction "1_1") (pintype "passive"))
      (node (ref "U$3") (pin "39/A20") (pinfunction "39/A20_39/A20") (pintype "bidirectional"))
    )
    (net (code "40") (name "Net-(M1A-S)") (class "Default")
      (node (ref "M1") (pin "1") (pinfunction "S_1") (pintype "passive"))
      (node (ref "X2") (pin "1") (pinfunction "KL_1") (pintype "passive"))
    )
    (net (code "41") (name "Net-(M1B-S)") (class "Default")
      (node (ref "M1") (pin "2") (pinfunction "S_2") (pintype "passive"))
      (node (ref "X2") (pin "2") (pinfunction "KL_2") (pintype "passive"))
    )
    (net (code "42") (name "Net-(M2A-S)") (class "Default")
      (node (ref "M2") (pin "1") (pinfunction "S_1") (pintype "passive"))
      (node (ref "X1") (pin "1") (pinfunction "KL_1") (pintype "passive"))
    )
    (net (code "43") (name "Net-(M2B-S)") (class "Default")
      (node (ref "M2") (pin "2") (pinfunction "S_2") (pintype "passive"))
      (node (ref "X1") (pin "2") (pinfunction "KL_2") (pintype "passive"))
    )
    (net (code "44") (name "Net-(M3A-S)") (class "Default")
      (node (ref "M3") (pin "1") (pinfunction "S_1") (pintype "passive"))
      (node (ref "X1") (pin "5") (pinfunction "KL_5") (pintype "passive"))
    )
    (net (code "45") (name "Net-(M3B-S)") (class "Default")
      (node (ref "M3") (pin "2") (pinfunction "S_2") (pintype "passive"))
      (node (ref "X1") (pin "6") (pinfunction "KL_6") (pintype "passive"))
    )
    (net (code "46") (name "Net-(M4A-S)") (class "Default")
      (node (ref "M4") (pin "1") (pinfunction "S_1") (pintype "passive"))
      (node (ref "X2") (pin "5") (pinfunction "KL_5") (pintype "passive"))
    )
    (net (code "47") (name "Net-(M4B-S)") (class "Default")
      (node (ref "M4") (pin "2") (pinfunction "S_2") (pintype "passive"))
      (node (ref "X2") (pin "6") (pinfunction "KL_6") (pintype "passive"))
    )
    (net (code "48") (name "Net-(Q3-B)") (class "Default")
      (node (ref "Q3") (pin "1") (pinfunction "B_1") (pintype "bidirectional"))
      (node (ref "R27") (pin "2") (pinfunction "2_2") (pintype "passive"))
    )
    (net (code "49") (name "Net-(Q3-C)") (class "Default")
      (node (ref "Q3") (pin "2") (pinfunction "C_2") (pintype "bidirectional"))
      (node (ref "R28") (pin "1") (pinfunction "1_1") (pintype "passive"))
      (node (ref "R29") (pin "1") (pinfunction "1_1") (pintype "passive"))
      (node (ref "R30") (pin "1") (pinfunction "1_1") (pintype "passive"))
    )
    (net (code "50") (name "Net-(R8-Pad1)") (class "Default")
      (node (ref "R8") (pin "1") (pinfunction "1_1") (pintype "passive"))
      (node (ref "U$2") (pin "D7") (pinfunction "D7_D7") (pintype "bidirectional"))
    )
    (net (code "51") (name "Net-(R15-Pad2)") (class "Default")
      (node (ref "R15") (pin "2") (pinfunction "2_2") (pintype "passive"))
      (node (ref "U$3") (pin "0/RX") (pinfunction "0/RX_0/RX") (pintype "bidirectional"))
    )
    (net (code "52") (name "Net-(R16-Pad2)") (class "Default")
      (node (ref "R16") (pin "2") (pinfunction "2_2") (pintype "passive"))
      (node (ref "U$3") (pin "1/TX") (pinfunction "1/TX_1/TX") (pintype "bidirectional"))
    )
    (net (code "53") (name "Net-(R20-Pad1)") (class "Default")
      (node (ref "R20") (pin "1") (pinfunction "1_1") (pintype "passive"))
      (node (ref "U$3") (pin "38/A19") (pinfunction "38/A19_38/A19") (pintype "bidirectional"))
    )
    (net (code "54") (name "Net-(R24-Pad1)") (class "Default")
      (node (ref "R24") (pin "1") (pinfunction "1_1") (pintype "passive"))
      (node (ref "U$3") (pin "37/A18") (pinfunction "37/A18_37/A18") (pintype "bidirectional"))
    )
    (net (code "55") (name "Net-(S2-P)") (class "Default")
      (node (ref "R27") (pin "1") (pinfunction "1_1") (pintype "passive"))
      (node (ref "S2") (pin "2") (pinfunction "P_2") (pintype "passive"))
    )
    (net (code "56") (name "Net-(SW-CONB-S)") (class "Default")
      (node (ref "FUSE") (pin "1") (pinfunction "1_1") (pintype "passive"))
      (node (ref "SW-CON") (pin "2") (pinfunction "S_2") (pintype "passive"))
    )
    (net (code "57") (name "Net-(T1-SECONDARY_1)") (class "Default")
      (node (ref "D8") (pin "A") (pinfunction "A_A") (pintype "passive"))
      (node (ref "T1") (pin "1") (pinfunction "SECONDARY_1_1") (pintype "bidirectional"))
    )
    (net (code "58") (name "RDCM") (class "Default")
      (node (ref "R5") (pin "1") (pinfunction "1_1") (pintype "passive"))
      (node (ref "U1") (pin "8") (pinfunction "RDCM_8") (pintype "input"))
    )
    (net (code "59") (name "RGB") (class "Default")
      (node (ref "C5") (pin "1") (pinfunction "1_1") (pintype "passive"))
      (node (ref "R1") (pin "2") (pinfunction "2_2") (pintype "passive"))
      (node (ref "U1") (pin "10") (pinfunction "RBG_10") (pintype "input"))
    )
    (net (code "60") (name "RVOUT") (class "Default")
      (node (ref "R4") (pin "1") (pinfunction "1_1") (pintype "passive"))
      (node (ref "U1") (pin "9") (pinfunction "RVOUT_9") (pintype "output"))
    )
    (net (code "61") (name "SCL") (class "Default")
      (node (ref "R22") (pin "2") (pinfunction "2_2") (pintype "passive"))
      (node (ref "U$3") (pin "19/A5/SCL") (pinfunction "19/A5/SCL_19/A5/SCL") (pintype "bidirectional"))
      (node (ref "U2") (pin "SCL") (pinfunction "SCL_SCL") (pintype "bidirectional"))
    )
    (net (code "62") (name "SDA") (class "Default")
      (node (ref "R23") (pin "2") (pinfunction "2_2") (pintype "passive"))
      (node (ref "U$3") (pin "18/A4/SDA") (pinfunction "18/A4/SDA_18/A4/SDA") (pintype "bidirectional"))
      (node (ref "U2") (pin "SDA") (pinfunction "SDA_SDA") (pintype "bidirectional"))
    )
    (net (code "63") (name "SINK") (class "Default")
      (node (ref "Q1") (pin "3") (pinfunction "D_3") (pintype "bidirectional"))
      (node (ref "R4") (pin "2") (pinfunction "2_2") (pintype "passive"))
      (node (ref "R5") (pin "2") (pinfunction "2_2") (pintype "passive"))
      (node (ref "T1") (pin "10") (pinfunction "PRIMARY_9_10") (pintype "bidirectional"))
      (node (ref "T1") (pin "7") (pinfunction "PRIMARY_6_7") (pintype "bidirectional"))
      (node (ref "T1") (pin "8") (pinfunction "PRIMARY_7_8") (pintype "bidirectional"))
      (node (ref "T1") (pin "9") (pinfunction "PRIMARY_8_9") (pintype "bidirectional"))
    )
    (net (code "64") (name "SOL_TRIG") (class "Default")
      (node (ref "R11") (pin "2") (pinfunction "2_2") (pintype "passive"))
      (node (ref "U$3") (pin "36/A17") (pinfunction "36/A17_36/A17") (pintype "bidirectional"))
    )
    (net (code "65") (name "SOURCE") (class "Default")
      (node (ref "Q1") (pin "2") (pinfunction "S_2") (pintype "bidirectional"))
      (node (ref "R6") (pin "2") (pinfunction "2_2") (pintype "passive"))
      (node (ref "U1") (pin "6") (pinfunction "SOURCE_6") (pintype "input"))
    )
    (net (code "66") (name "VBAT+") (class "Default")
      (node (ref "SW-CON") (pin "1") (pinfunction "S_1") (pintype "passive"))
      (node (ref "VBAT") (pin "1") (pinfunction "KL_1") (pintype "passive"))
      (node (ref "VBAT2") (pin "+") (pinfunction "VCC_+") (pintype "bidirectional"))
    )
    (net (code "67") (name "VTRANS") (class "Default")
      (node (ref "C1") (pin "+") (pinfunction "+_+") (pintype "passive"))
      (node (ref "C2") (pin "+") (pinfunction "+_+") (pintype "passive"))
      (node (ref "C3") (pin "+") (pinfunction "+_+") (pintype "passive"))
      (node (ref "C4") (pin "1") (pinfunction "1_1") (pintype "passive"))
      (node (ref "C6") (pin "1") (pinfunction "1_1") (pintype "passive"))
      (node (ref "GT_DRIVER") (pin "8") (pinfunction "VCC_8") (pintype "bidirectional"))
      (node (ref "R9") (pin "2") (pinfunction "2_2") (pintype "passive"))
      (node (ref "S2") (pin "3") (pinfunction "S_3") (pintype "passive"))
      (node (ref "SWITCH") (pin "3") (pinfunction "S_3") (pintype "passive"))
      (node (ref "SWITCH") (pin "6") (pinfunction "S_6") (pintype "passive"))
      (node (ref "T1") (pin "3") (pinfunction "PRIMARY_2_3") (pintype "bidirectional"))
      (node (ref "T1") (pin "4") (pinfunction "PRIMARY_3_4") (pintype "bidirectional"))
      (node (ref "T1") (pin "5") (pinfunction "PRIMARY_4_5") (pintype "bidirectional"))
      (node (ref "T1") (pin "6") (pinfunction "PRIMARY_5_6") (pintype "bidirectional"))
      (node (ref "U1") (pin "1") (pinfunction "VTRANS_1") (pintype "power_in"))
      (node (ref "U1") (pin "4") (pinfunction "VCC_4") (pintype "power_in"))
      (node (ref "VT_D") (pin "1") (pinfunction "1_1") (pintype "passive"))
      (node (ref "VT_D") (pin "2") (pinfunction "2_2") (pintype "passive"))
    )
    (net (code "68") (name "unconnected-(GT_DRIVER-N{slash}C_1-Pad1)") (class "Default")
      (node (ref "GT_DRIVER") (pin "1") (pinfunction "N/C_1_1") (pintype "bidirectional"))
    )
    (net (code "69") (name "unconnected-(GT_DRIVER-N{slash}C_2-Pad4)") (class "Default")
      (node (ref "GT_DRIVER") (pin "4") (pinfunction "N/C_2_4") (pintype "bidirectional"))
    )
    (net (code "70") (name "unconnected-(GT_DRIVER-VO_2-Pad7)") (class "Default")
      (node (ref "GT_DRIVER") (pin "7") (pinfunction "VO_2_7") (pintype "bidirectional"))
    )
    (net (code "71") (name "unconnected-(SWITCHA-O-Pad1)") (class "Default")
      (node (ref "SWITCH") (pin "1") (pinfunction "O_1") (pintype "passive"))
    )
    (net (code "72") (name "unconnected-(SWITCHB-O-Pad4)") (class "Default")
      (node (ref "SWITCH") (pin "4") (pinfunction "O_4") (pintype "passive"))
    )
    (net (code "73") (name "unconnected-(T1-PRIMARY_1-Pad2)") (class "Default")
      (node (ref "T1") (pin "2") (pinfunction "PRIMARY_1_2") (pintype "bidirectional"))
    )
    (net (code "74") (name "unconnected-(T1-PRIMARY_10-Pad11)") (class "Default")
      (node (ref "T1") (pin "11") (pinfunction "PRIMARY_10_11") (pintype "bidirectional"))
    )
    (net (code "75") (name "unconnected-(U$2-3V3-Pad3V3@0)") (class "Default")
      (node (ref "U$2") (pin "3V3@0") (pinfunction "3V3_3V3@0") (pintype "bidirectional"))
    )
    (net (code "76") (name "unconnected-(U$2-3V3-Pad3V3@1)") (class "Default")
      (node (ref "U$2") (pin "3V3@1") (pinfunction "3V3_3V3@1") (pintype "bidirectional"))
    )
    (net (code "77") (name "unconnected-(U$2-3V3-Pad3V3@2)") (class "Default")
      (node (ref "U$2") (pin "3V3@2") (pinfunction "3V3_3V3@2") (pintype "bidirectional"))
    )
    (net (code "78") (name "unconnected-(U$2-GND-PadGND@0)") (class "Default")
      (node (ref "U$2") (pin "GND@0") (pinfunction "GND_GND@0") (pintype "bidirectional"))
    )
    (net (code "79") (name "unconnected-(U$2-PadAD0)") (class "Default")
      (node (ref "U$2") (pin "AD0") (pinfunction "AD0_AD0") (pintype "bidirectional"))
    )
    (net (code "80") (name "unconnected-(U$2-PadCLK)") (class "Default")
      (node (ref "U$2") (pin "CLK") (pinfunction "CLK_CLK") (pintype "bidirectional"))
    )
    (net (code "81") (name "unconnected-(U$2-PadCMD)") (class "Default")
      (node (ref "U$2") (pin "CMD") (pinfunction "CMD_CMD") (pintype "bidirectional"))
    )
    (net (code "82") (name "unconnected-(U$2-PadD0)") (class "Default")
      (node (ref "U$2") (pin "D0") (pinfunction "D0_D0") (pintype "bidirectional"))
    )
    (net (code "83") (name "unconnected-(U$2-PadD1)") (class "Default")
      (node (ref "U$2") (pin "D1") (pinfunction "D1_D1") (pintype "bidirectional"))
    )
    (net (code "84") (name "unconnected-(U$2-PadD2)") (class "Default")
      (node (ref "U$2") (pin "D2") (pinfunction "D2_D2") (pintype "bidirectional"))
    )
    (net (code "85") (name "unconnected-(U$2-PadD3)") (class "Default")
      (node (ref "U$2") (pin "D3") (pinfunction "D3_D3") (pintype "bidirectional"))
    )
    (net (code "86") (name "unconnected-(U$2-PadD4)") (class "Default")
      (node (ref "U$2") (pin "D4") (pinfunction "D4_D4") (pintype "bidirectional"))
    )
    (net (code "87") (name "unconnected-(U$2-PadD5)") (class "Default")
      (node (ref "U$2") (pin "D5") (pinfunction "D5_D5") (pintype "bidirectional"))
    )
    (net (code "88") (name "unconnected-(U$2-PadD6)") (class "Default")
      (node (ref "U$2") (pin "D6") (pinfunction "D6_D6") (pintype "bidirectional"))
    )
    (net (code "89") (name "unconnected-(U$2-PadD8)") (class "Default")
      (node (ref "U$2") (pin "D8") (pinfunction "D8_D8") (pintype "bidirectional"))
    )
    (net (code "90") (name "unconnected-(U$2-PadEN)") (class "Default")
      (node (ref "U$2") (pin "EN") (pinfunction "EN_EN") (pintype "bidirectional"))
    )
    (net (code "91") (name "unconnected-(U$2-PadRST)") (class "Default")
      (node (ref "U$2") (pin "RST") (pinfunction "RST_RST") (pintype "bidirectional"))
    )
    (net (code "92") (name "unconnected-(U$2-PadSD0)") (class "Default")
      (node (ref "U$2") (pin "SD0") (pinfunction "SD0_SD0") (pintype "bidirectional"))
    )
    (net (code "93") (name "unconnected-(U$2-PadSD1)") (class "Default")
      (node (ref "U$2") (pin "SD1") (pinfunction "SD1_SD1") (pintype "bidirectional"))
    )
    (net (code "94") (name "unconnected-(U$2-PadSD2)") (class "Default")
      (node (ref "U$2") (pin "SD2") (pinfunction "SD2_SD2") (pintype "bidirectional"))
    )
    (net (code "95") (name "unconnected-(U$2-PadSD3)") (class "Default")
      (node (ref "U$2") (pin "SD3") (pinfunction "SD3_SD3") (pintype "bidirectional"))
    )
    (net (code "96") (name "unconnected-(U$2-RSV-PadRSV@0)") (class "Default")
      (node (ref "U$2") (pin "RSV@0") (pinfunction "RSV_RSV@0") (pintype "bidirectional"))
    )
    (net (code "97") (name "unconnected-(U$2-RSV-PadRSV@1)") (class "Default")
      (node (ref "U$2") (pin "RSV@1") (pinfunction "RSV_RSV@1") (pintype "bidirectional"))
    )
    (net (code "98") (name "unconnected-(U$3-A21{slash}DAC0-Pad21{slash}DAC0)") (class "Default")
      (node (ref "U$3") (pin "21/DAC0") (pinfunction "A21/DAC0_21/DAC0") (pintype "bidirectional"))
    )
    (net (code "99") (name "unconnected-(U$3-Pad3V3)") (class "Default")
      (node (ref "U$3") (pin "3V3") (pinfunction "3V3_3V3") (pintype "bidirectional"))
    )
    (net (code "100") (name "unconnected-(U$3-Pad3V3_LO)") (class "Default")
      (node (ref "U$3") (pin "3V3_LO") (pinfunction "3V3_LO_3V3_LO") (pintype "bidirectional"))
    )
    (net (code "101") (name "unconnected-(U$3-Pad7)") (class "Default")
      (node (ref "U$3") (pin "7") (pinfunction "7_7") (pintype "bidirectional"))
    )
    (net (code "102") (name "unconnected-(U$3-Pad8)") (class "Default")
      (node (ref "U$3") (pin "8") (pinfunction "8_8") (pintype "bidirectional"))
    )
    (net (code "103") (name "unconnected-(U$3-Pad11{slash}MOSI)") (class "Default")
      (node (ref "U$3") (pin "11/MOSI") (pinfunction "11/MOSI_11/MOSI") (pintype "bidirectional"))
    )
    (net (code "104") (name "unconnected-(U$3-Pad12{slash}MISO)") (class "Default")
      (node (ref "U$3") (pin "12/MISO") (pinfunction "12/MISO_12/MISO") (pintype "bidirectional"))
    )
    (net (code "105") (name "unconnected-(U$3-Pad13{slash}SCK)") (class "Default")
      (node (ref "U$3") (pin "13/SCK") (pinfunction "13/SCK_13/SCK") (pintype "bidirectional"))
    )
    (net (code "106") (name "unconnected-(U$3-Pad14{slash}A0)") (class "Default")
      (node (ref "U$3") (pin "14/A0") (pinfunction "14/A0_14/A0") (pintype "bidirectional"))
    )
    (net (code "107") (name "unconnected-(U$3-Pad15{slash}A1)") (class "Default")
      (node (ref "U$3") (pin "15/A1") (pinfunction "15/A1_15/A1") (pintype "bidirectional"))
    )
    (net (code "108") (name "unconnected-(U$3-Pad16{slash}A2)") (class "Default")
      (node (ref "U$3") (pin "16/A2") (pinfunction "16/A2_16/A2") (pintype "bidirectional"))
    )
    (net (code "109") (name "unconnected-(U$3-Pad24)") (class "Default")
      (node (ref "U$3") (pin "24") (pinfunction "24_24") (pintype "bidirectional"))
    )
    (net (code "110") (name "unconnected-(U$3-Pad25)") (class "Default")
      (node (ref "U$3") (pin "25") (pinfunction "25_25") (pintype "bidirectional"))
    )
    (net (code "111") (name "unconnected-(U$3-Pad26)") (class "Default")
      (node (ref "U$3") (pin "26") (pinfunction "26_26") (pintype "bidirectional"))
    )
    (net (code "112") (name "unconnected-(U$3-Pad27)") (class "Default")
      (node (ref "U$3") (pin "27") (pinfunction "27_27") (pintype "bidirectional"))
    )
    (net (code "113") (name "unconnected-(U$3-Pad28)") (class "Default")
      (node (ref "U$3") (pin "28") (pinfunction "28_28") (pintype "bidirectional"))
    )
    (net (code "114") (name "unconnected-(U$3-Pad29)") (class "Default")
      (node (ref "U$3") (pin "29") (pinfunction "29_29") (pintype "bidirectional"))
    )
    (net (code "115") (name "unconnected-(U$3-Pad30)") (class "Default")
      (node (ref "U$3") (pin "30") (pinfunction "30_30") (pintype "bidirectional"))
    )
    (net (code "116") (name "unconnected-(U$3-Pad31{slash}A12)") (class "Default")
      (node (ref "U$3") (pin "31/A12") (pinfunction "31/A12_31/A12") (pintype "bidirectional"))
    )
    (net (code "117") (name "unconnected-(U$3-Pad32{slash}A13)") (class "Default")
      (node (ref "U$3") (pin "32/A13") (pinfunction "32/A13_32/A13") (pintype "bidirectional"))
    )
    (net (code "118") (name "unconnected-(U$3-Pad33{slash}A14)") (class "Default")
      (node (ref "U$3") (pin "33/A14") (pinfunction "33/A14_33/A14") (pintype "bidirectional"))
    )
    (net (code "119") (name "unconnected-(U$3-Pad34{slash}A15)") (class "Default")
      (node (ref "U$3") (pin "34/A15") (pinfunction "34/A15_34/A15") (pintype "bidirectional"))
    )
    (net (code "120") (name "unconnected-(U$3-PadA10)") (class "Default")
      (node (ref "U$3") (pin "A10") (pinfunction "A10_A10") (pintype "bidirectional"))
    )
    (net (code "121") (name "unconnected-(U$3-PadA11)") (class "Default")
      (node (ref "U$3") (pin "A11") (pinfunction "A11_A11") (pintype "bidirectional"))
    )
    (net (code "122") (name "unconnected-(U$3-PadA22{slash}DAC1)") (class "Default")
      (node (ref "U$3") (pin "A22/DAC1") (pinfunction "A22/DAC1_A22/DAC1") (pintype "bidirectional"))
    )
    (net (code "123") (name "unconnected-(U$3-PadAREF)") (class "Default")
      (node (ref "U$3") (pin "AREF") (pinfunction "AREF_AREF") (pintype "bidirectional"))
    )
    (net (code "124") (name "unconnected-(U$3-PadVUSB)") (class "Default")
      (node (ref "U$3") (pin "VUSB") (pinfunction "VUSB_VUSB") (pintype "bidirectional"))
    )
    (net (code "125") (name "unconnected-(U2-PadADO)") (class "Default")
      (node (ref "U2") (pin "ADO") (pinfunction "ADO_ADO") (pintype "bidirectional"))
    )
    (net (code "126") (name "unconnected-(U2-PadXCL)") (class "Default")
      (node (ref "U2") (pin "XCL") (pinfunction "XCL_XCL") (pintype "bidirectional"))
    )
    (net (code "127") (name "unconnected-(U2-PadXDA)") (class "Default")
      (node (ref "U2") (pin "XDA") (pinfunction "XDA_XDA") (pintype "bidirectional"))
    )
  )
)
